# SHASwitch2.net
KiCad netlist of a schematic drawn in EAGLE
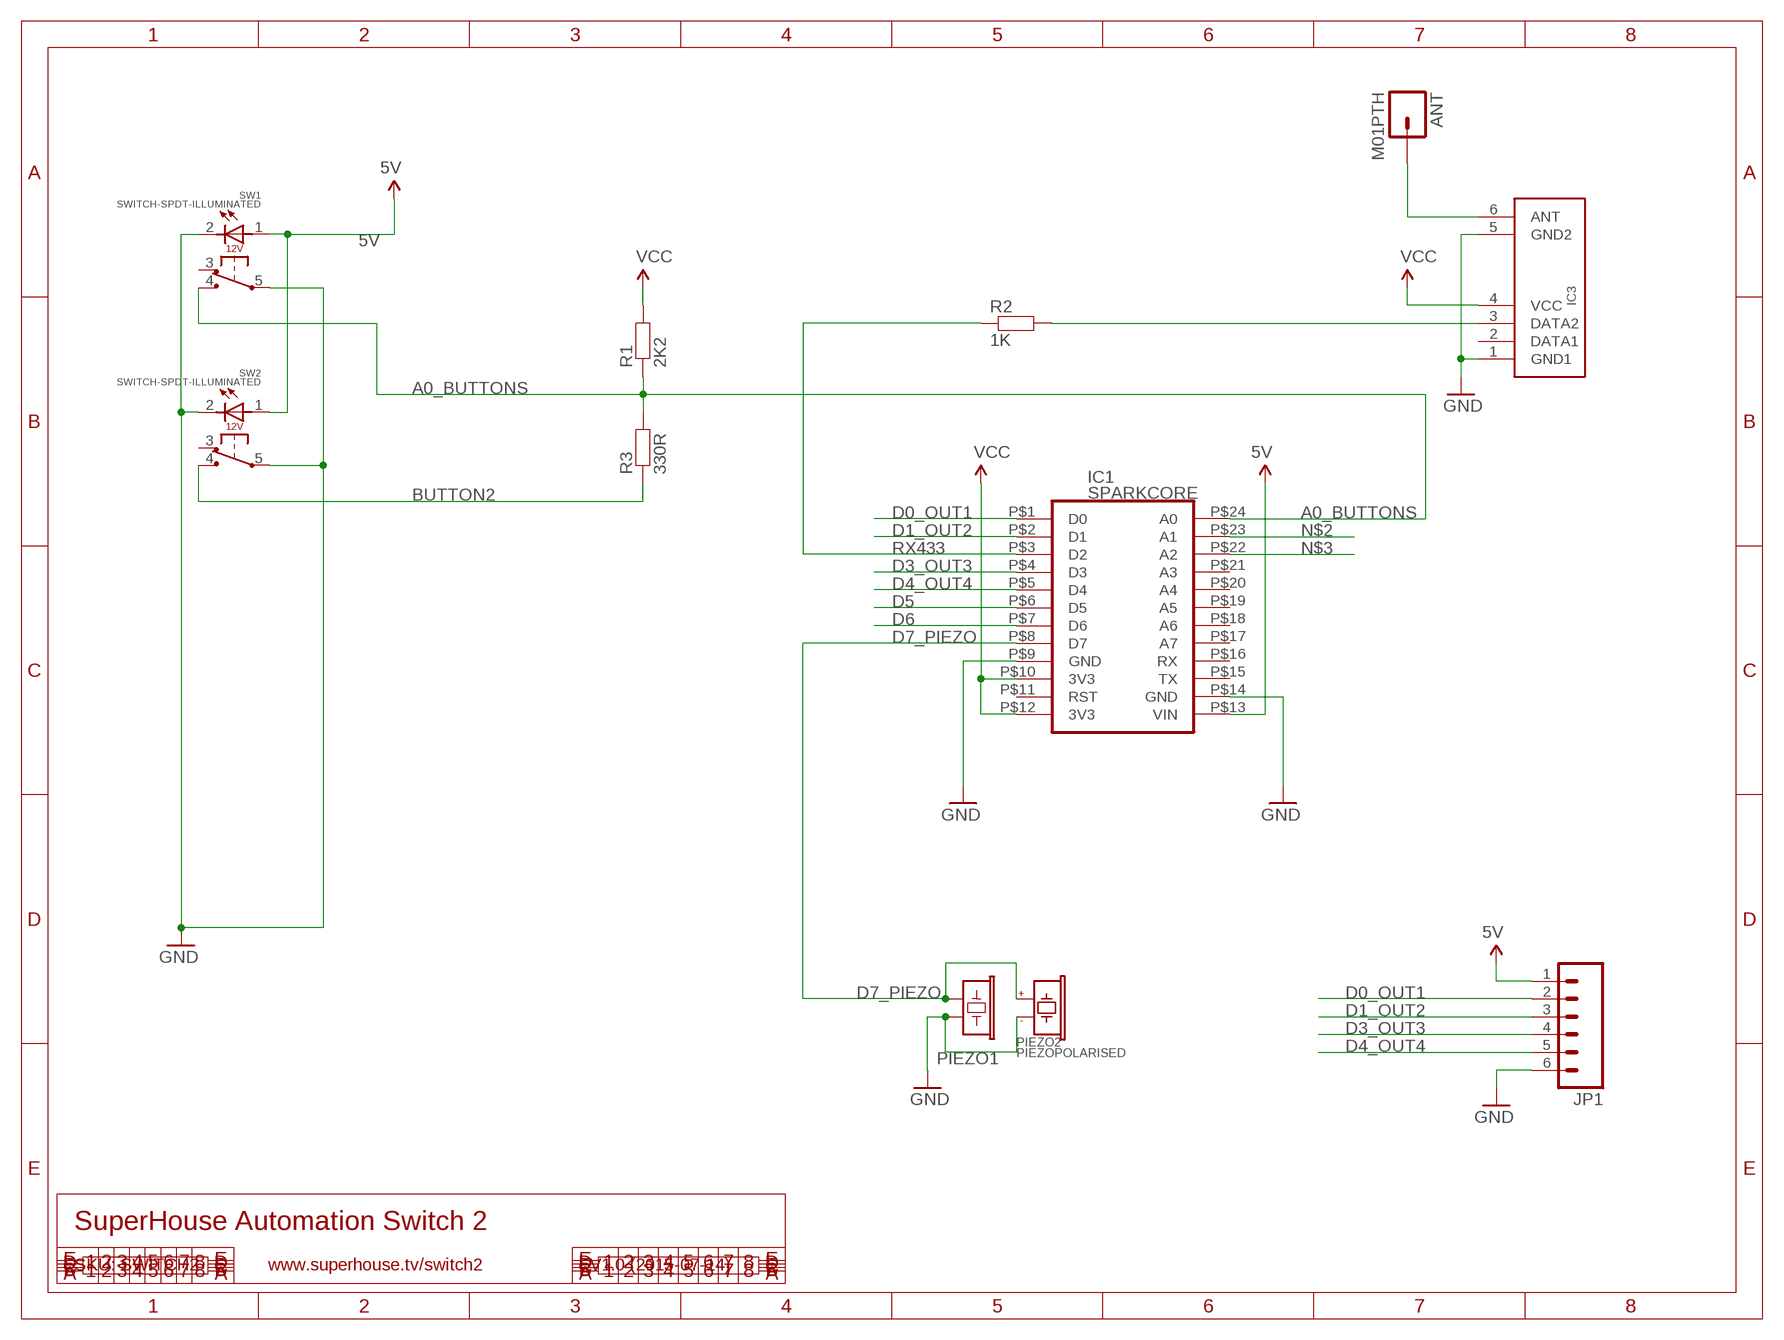
[diagram p0: schematic, sheet 1]

(export (version "E")
  (design (tool "Eeschema 10.0.6"))
  (components
    (comp (ref "ANT")
      (value "M01PTH")
      (footprint "eagle-import:1X01")
      (libsource (lib "eagle-import") (part "M01PTH"))
    )
    (comp (ref "IC1")
      (value "SPARKCORE")
      (footprint "eagle-import:SPARKCORE")
      (libsource (lib "eagle-import") (part "SPARKCORE"))
    )
    (comp (ref "IC3")
      (value "RXB1")
      (footprint "eagle-import:RX-B1-SHORT-FLAT")
      (libsource (lib "eagle-import") (part "RXB1SHORTFLAT"))
    )
    (comp (ref "JP1")
      (value "M06SIP")
      (footprint "eagle-import:1X06")
      (libsource (lib "eagle-import") (part "M06SIP"))
    )
    (comp (ref "PIEZO1")
      (value "BUZZERSMD12X12")
      (footprint "eagle-import:BUZZER-12X12-SMT")
      (libsource (lib "eagle-import") (part "BUZZERSMD12X12"))
    )
    (comp (ref "PIEZO2")
      (value "PIEZOPOLARISED")
      (footprint "eagle-import:PIEZO12MMWIDEPOLARISED")
      (libsource (lib "eagle-import") (part "PIEZOPOLARISED"))
    )
    (comp (ref "R1")
      (value "2K2")
      (footprint "eagle-import:0603")
      (libsource (lib "eagle-import") (part "RESISTOR0603"))
    )
    (comp (ref "R2")
      (value "1K")
      (footprint "eagle-import:0603")
      (libsource (lib "eagle-import") (part "RESISTOR0603"))
    )
    (comp (ref "R3")
      (value "330R")
      (footprint "eagle-import:0603")
      (libsource (lib "eagle-import") (part "RESISTOR0603"))
    )
    (comp (ref "SW1")
      (value "SWITCH-SPDT-ILLUMINATED")
      (footprint "eagle-import:SWITCH-SPDT-ILLUMINATED")
      (libsource (lib "eagle-import") (part "SWITCH-SPDT-ILLUMINATED"))
    )
    (comp (ref "SW2")
      (value "SWITCH-SPDT-ILLUMINATED")
      (footprint "eagle-import:SWITCH-SPDT-ILLUMINATED")
      (libsource (lib "eagle-import") (part "SWITCH-SPDT-ILLUMINATED"))
    )
  )
  (nets
    (net (code "1") (name "/A0_BUTTONS") (class "Default")
      (node (ref "IC1") (pin "P$24") (pinfunction "A0_P$24") (pintype "bidirectional"))
      (node (ref "R1") (pin "1") (pinfunction "1_1") (pintype "passive"))
      (node (ref "R3") (pin "2") (pinfunction "2_2") (pintype "passive"))
      (node (ref "SW1") (pin "4") (pinfunction "NO_4") (pintype "passive"))
    )
    (net (code "2") (name "/BUTTON2") (class "Default")
      (node (ref "R3") (pin "1") (pinfunction "1_1") (pintype "passive"))
      (node (ref "SW2") (pin "4") (pinfunction "NO_4") (pintype "passive"))
    )
    (net (code "3") (name "/D0_OUT1") (class "Default")
      (node (ref "IC1") (pin "P$1") (pinfunction "D0_P$1") (pintype "bidirectional"))
      (node (ref "JP1") (pin "2") (pinfunction "2_2") (pintype "passive"))
    )
    (net (code "4") (name "/D1_OUT2") (class "Default")
      (node (ref "IC1") (pin "P$2") (pinfunction "D1_P$2") (pintype "bidirectional"))
      (node (ref "JP1") (pin "3") (pinfunction "3_3") (pintype "passive"))
    )
    (net (code "5") (name "/D3_OUT3") (class "Default")
      (node (ref "IC1") (pin "P$4") (pinfunction "D3_P$4") (pintype "bidirectional"))
      (node (ref "JP1") (pin "4") (pinfunction "4_4") (pintype "passive"))
    )
    (net (code "6") (name "/D4_OUT4") (class "Default")
      (node (ref "IC1") (pin "P$5") (pinfunction "D4_P$5") (pintype "bidirectional"))
      (node (ref "JP1") (pin "5") (pinfunction "5_5") (pintype "passive"))
    )
    (net (code "7") (name "/D5") (class "Default")
      (node (ref "IC1") (pin "P$6") (pinfunction "D5_P$6") (pintype "bidirectional"))
    )
    (net (code "8") (name "/D6") (class "Default")
      (node (ref "IC1") (pin "P$7") (pinfunction "D6_P$7") (pintype "bidirectional"))
    )
    (net (code "9") (name "/D7_PIEZO") (class "Default")
      (node (ref "IC1") (pin "P$8") (pinfunction "D7_P$8") (pintype "bidirectional"))
      (node (ref "PIEZO1") (pin "1") (pinfunction "1_1") (pintype "passive"))
      (node (ref "PIEZO2") (pin "1") (pinfunction "+_1") (pintype "bidirectional"))
    )
    (net (code "10") (name "/N$2") (class "Default")
      (node (ref "IC1") (pin "P$23") (pinfunction "A1_P$23") (pintype "bidirectional"))
    )
    (net (code "11") (name "/N$3") (class "Default")
      (node (ref "IC1") (pin "P$22") (pinfunction "A2_P$22") (pintype "bidirectional"))
    )
    (net (code "12") (name "/RX433") (class "Default")
      (node (ref "IC1") (pin "P$3") (pinfunction "D2_P$3") (pintype "bidirectional"))
      (node (ref "R2") (pin "1") (pinfunction "1_1") (pintype "passive"))
    )
    (net (code "13") (name "5V") (class "Default")
      (node (ref "IC1") (pin "P$13") (pinfunction "VIN_P$13") (pintype "bidirectional"))
      (node (ref "JP1") (pin "1") (pinfunction "1_1") (pintype "passive"))
      (node (ref "SW1") (pin "1") (pinfunction "+_1") (pintype "passive"))
      (node (ref "SW2") (pin "1") (pinfunction "+_1") (pintype "passive"))
    )
    (net (code "14") (name "GND") (class "Default")
      (node (ref "IC1") (pin "P$14") (pinfunction "GND_P$14") (pintype "bidirectional"))
      (node (ref "IC1") (pin "P$9") (pinfunction "GND_P$9") (pintype "bidirectional"))
      (node (ref "IC3") (pin "1") (pinfunction "GND1_1") (pintype "bidirectional"))
      (node (ref "IC3") (pin "5") (pinfunction "GND2_5") (pintype "bidirectional"))
      (node (ref "JP1") (pin "6") (pinfunction "6_6") (pintype "passive"))
      (node (ref "PIEZO1") (pin "2") (pinfunction "2_2") (pintype "passive"))
      (node (ref "PIEZO2") (pin "2") (pinfunction "-_2") (pintype "bidirectional"))
      (node (ref "SW1") (pin "2") (pinfunction "-_2") (pintype "passive"))
      (node (ref "SW1") (pin "5") (pinfunction "COM_5") (pintype "passive"))
      (node (ref "SW2") (pin "2") (pinfunction "-_2") (pintype "passive"))
      (node (ref "SW2") (pin "5") (pinfunction "COM_5") (pintype "passive"))
    )
    (net (code "15") (name "Net-(IC3-ANT)") (class "Default")
      (node (ref "ANT") (pin "1") (pinfunction "1_1") (pintype "passive"))
      (node (ref "IC3") (pin "6") (pinfunction "ANT_6") (pintype "bidirectional"))
    )
    (net (code "16") (name "Net-(IC3-DATA2)") (class "Default")
      (node (ref "IC3") (pin "3") (pinfunction "DATA2_3") (pintype "bidirectional"))
      (node (ref "R2") (pin "2") (pinfunction "2_2") (pintype "passive"))
    )
    (net (code "17") (name "VCC") (class "Default")
      (node (ref "IC1") (pin "P$10") (pinfunction "3V3_P$10") (pintype "bidirectional"))
      (node (ref "IC1") (pin "P$12") (pinfunction "3V3_P$12") (pintype "bidirectional"))
      (node (ref "IC3") (pin "4") (pinfunction "VCC_4") (pintype "bidirectional"))
      (node (ref "R1") (pin "2") (pinfunction "2_2") (pintype "passive"))
    )
    (net (code "18") (name "unconnected-(IC1-A3-PadP$21)") (class "Default")
      (node (ref "IC1") (pin "P$21") (pinfunction "A3_P$21") (pintype "bidirectional"))
    )
    (net (code "19") (name "unconnected-(IC1-A4-PadP$20)") (class "Default")
      (node (ref "IC1") (pin "P$20") (pinfunction "A4_P$20") (pintype "bidirectional"))
    )
    (net (code "20") (name "unconnected-(IC1-A5-PadP$19)") (class "Default")
      (node (ref "IC1") (pin "P$19") (pinfunction "A5_P$19") (pintype "bidirectional"))
    )
    (net (code "21") (name "unconnected-(IC1-A6-PadP$18)") (class "Default")
      (node (ref "IC1") (pin "P$18") (pinfunction "A6_P$18") (pintype "bidirectional"))
    )
    (net (code "22") (name "unconnected-(IC1-A7-PadP$17)") (class "Default")
      (node (ref "IC1") (pin "P$17") (pinfunction "A7_P$17") (pintype "bidirectional"))
    )
    (net (code "23") (name "unconnected-(IC1-RST-PadP$11)") (class "Default")
      (node (ref "IC1") (pin "P$11") (pinfunction "RST_P$11") (pintype "bidirectional"))
    )
    (net (code "24") (name "unconnected-(IC1-RX-PadP$16)") (class "Default")
      (node (ref "IC1") (pin "P$16") (pinfunction "RX_P$16") (pintype "bidirectional"))
    )
    (net (code "25") (name "unconnected-(IC1-TX-PadP$15)") (class "Default")
      (node (ref "IC1") (pin "P$15") (pinfunction "TX_P$15") (pintype "bidirectional"))
    )
    (net (code "26") (name "unconnected-(IC3-DATA1-Pad2)") (class "Default")
      (node (ref "IC3") (pin "2") (pinfunction "DATA1_2") (pintype "bidirectional"))
    )
    (net (code "27") (name "unconnected-(SW1-NC-Pad3)") (class "Default")
      (node (ref "SW1") (pin "3") (pinfunction "NC_3") (pintype "passive"))
    )
    (net (code "28") (name "unconnected-(SW2-NC-Pad3)") (class "Default")
      (node (ref "SW2") (pin "3") (pinfunction "NC_3") (pintype "passive"))
    )
  )
)
